# mainboard-raspi-2.net
KiCad netlist of a schematic drawn in EAGLE
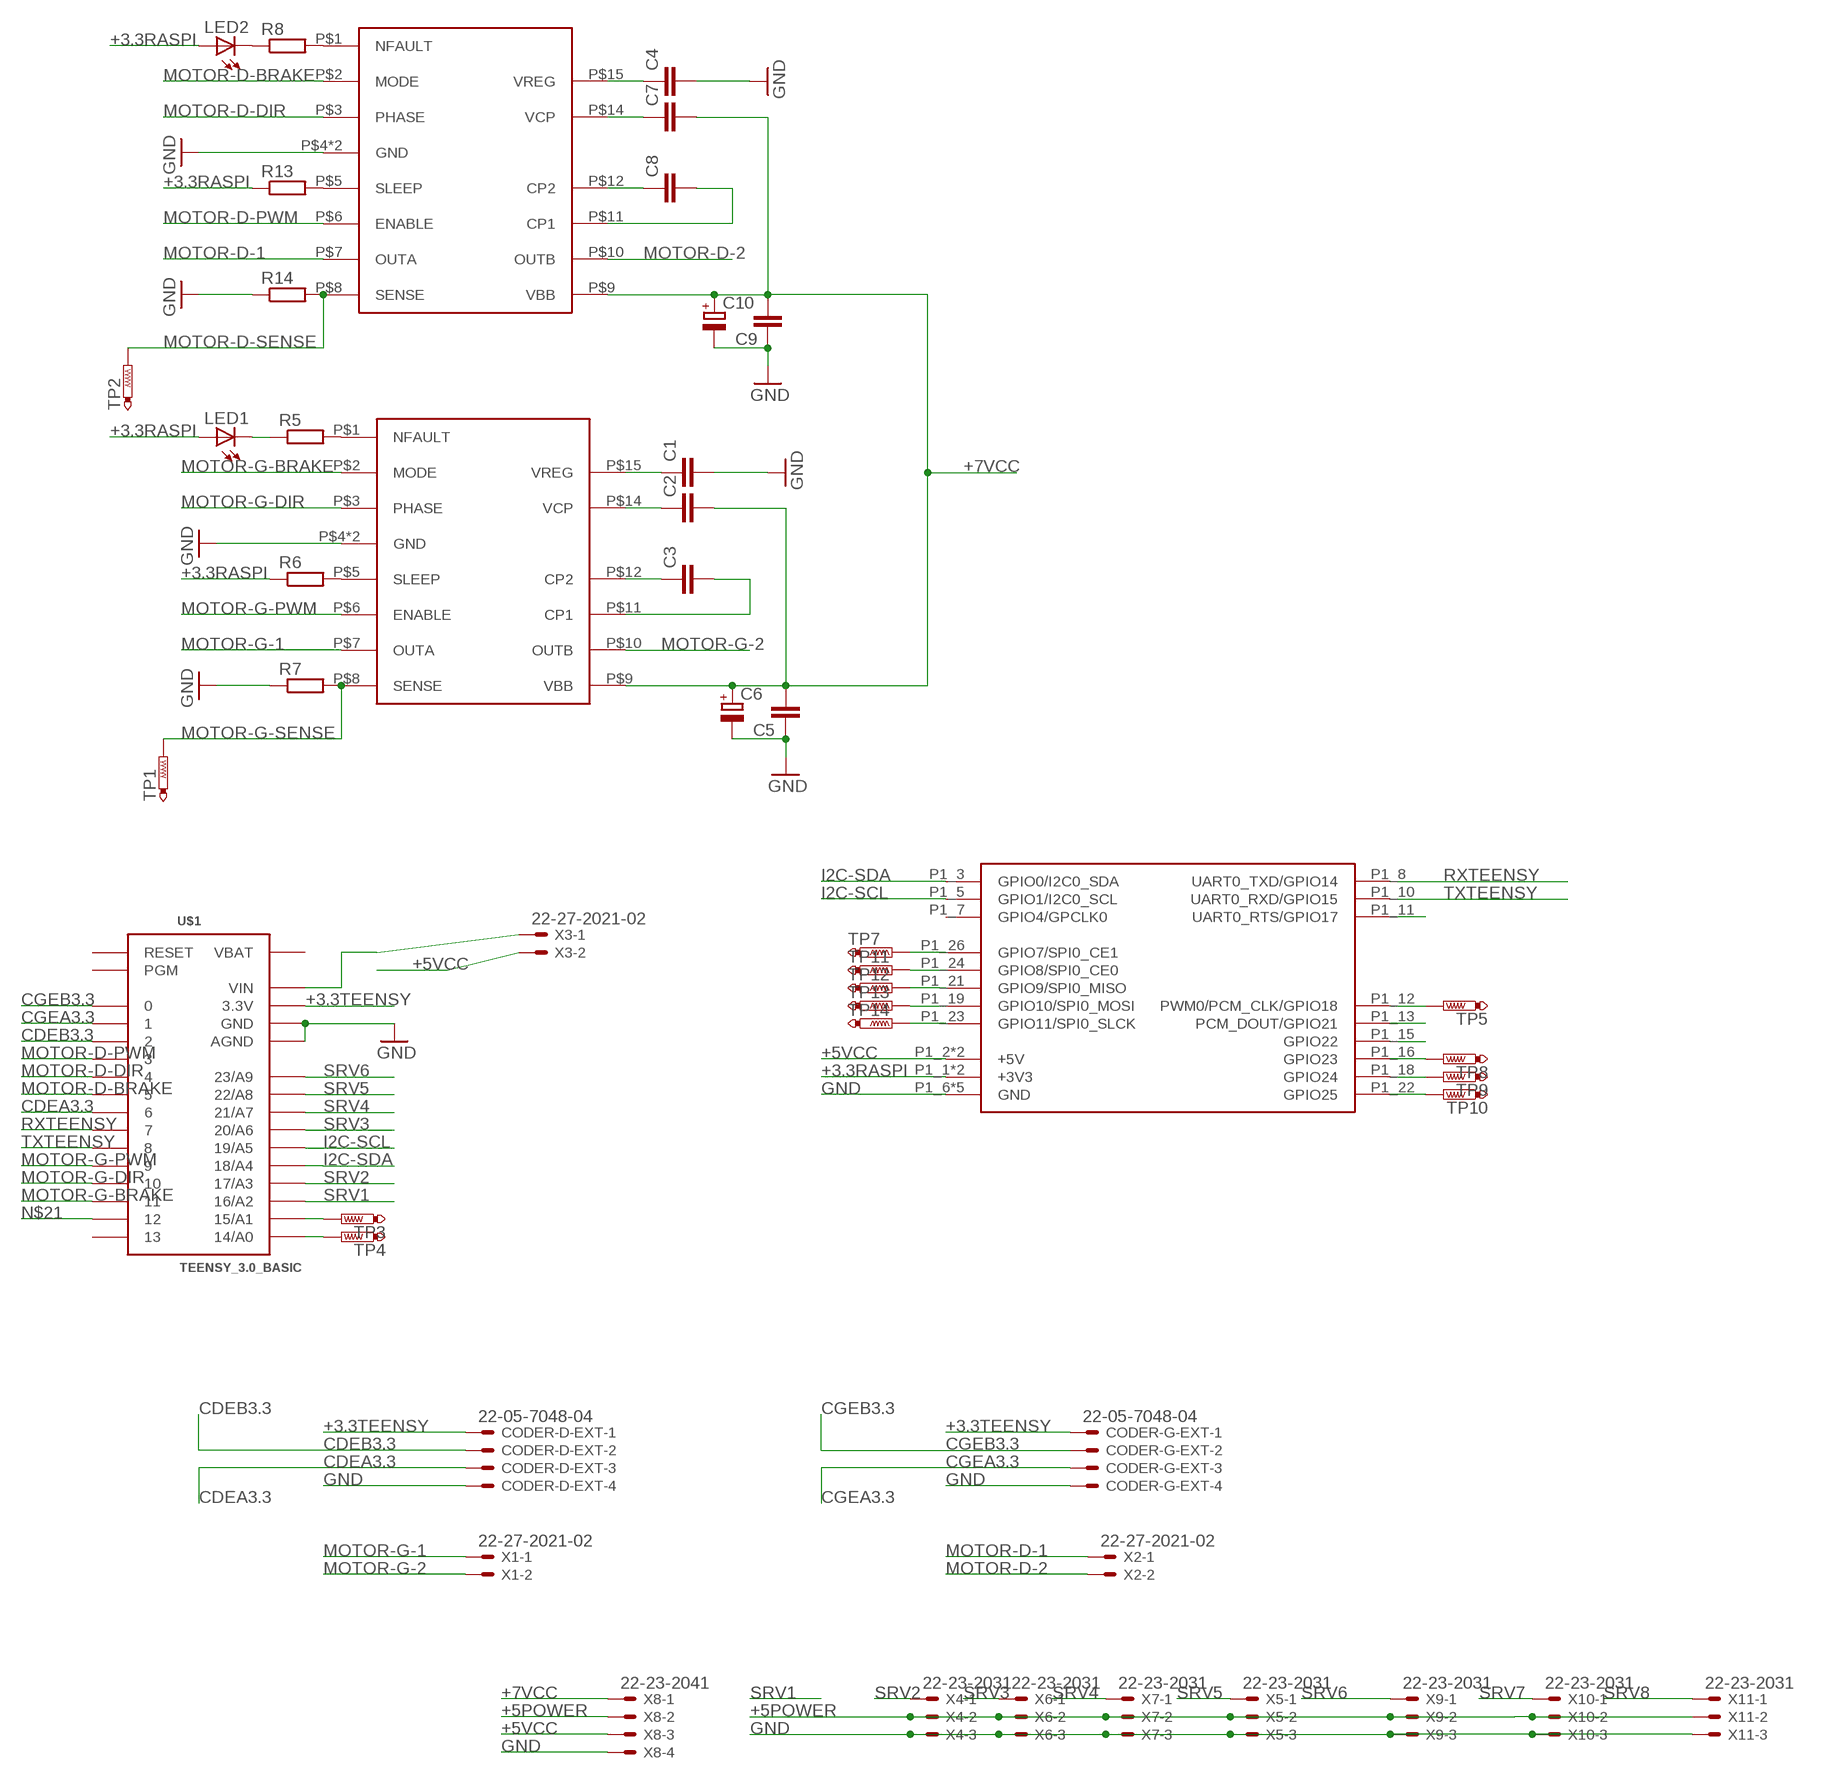
[diagram p0: schematic, sheet 1]

(export (version "E")
  (design (tool "Eeschema 10.0.6"))
  (components
    (comp (ref "C1")
      (value "C-EUC0805K")
      (footprint "eagle-import:C0805K")
      (libsource (lib "eagle-import") (part "C-EUC0805K"))
    )
    (comp (ref "C2")
      (value "C-EUC0805K")
      (footprint "eagle-import:C0805K")
      (libsource (lib "eagle-import") (part "C-EUC0805K"))
    )
    (comp (ref "C3")
      (value "C-EUC0805K")
      (footprint "eagle-import:C0805K")
      (libsource (lib "eagle-import") (part "C-EUC0805K"))
    )
    (comp (ref "C4")
      (value "C-EUC0805K")
      (footprint "eagle-import:C0805K")
      (libsource (lib "eagle-import") (part "C-EUC0805K"))
    )
    (comp (ref "C5")
      (value "C-EUC0805K")
      (footprint "eagle-import:C0805K")
      (libsource (lib "eagle-import") (part "C-EUC0805K"))
    )
    (comp (ref "C6")
      (value "CPOL-EUE3.5-8")
      (footprint "eagle-import:E3,5-8")
      (libsource (lib "eagle-import") (part "CPOL-EUE3.5-8"))
    )
    (comp (ref "C7")
      (value "C-EUC0805K")
      (footprint "eagle-import:C0805K")
      (libsource (lib "eagle-import") (part "C-EUC0805K"))
    )
    (comp (ref "C8")
      (value "C-EUC0805K")
      (footprint "eagle-import:C0805K")
      (libsource (lib "eagle-import") (part "C-EUC0805K"))
    )
    (comp (ref "C9")
      (value "C-EUC0805K")
      (footprint "eagle-import:C0805K")
      (libsource (lib "eagle-import") (part "C-EUC0805K"))
    )
    (comp (ref "C10")
      (value "CPOL-EUE3.5-8")
      (footprint "eagle-import:E3,5-8")
      (libsource (lib "eagle-import") (part "CPOL-EUE3.5-8"))
    )
    (comp (ref "CODER-D-EXT")
      (value "22-05-7048-04")
      (footprint "eagle-import:7395-04")
      (libsource (lib "eagle-import") (part "22-?-0405-7048"))
    )
    (comp (ref "CODER-G-EXT")
      (value "22-05-7048-04")
      (footprint "eagle-import:7395-04")
      (libsource (lib "eagle-import") (part "22-?-0405-7048"))
    )
    (comp (ref "LED1")
      (value "LED3MM")
      (footprint "eagle-import:LED3MM")
      (libsource (lib "eagle-import") (part "LED3MM"))
    )
    (comp (ref "LED2")
      (value "LED3MM")
      (footprint "eagle-import:LED3MM")
      (libsource (lib "eagle-import") (part "LED3MM"))
    )
    (comp (ref "R5")
      (value "R-EU_R0805W")
      (footprint "eagle-import:R0805W")
      (libsource (lib "eagle-import") (part "R-EU_R0805W"))
    )
    (comp (ref "R6")
      (value "R-EU_0204/7")
      (footprint "eagle-import:0204_7")
      (libsource (lib "eagle-import") (part "R-EU_0204/7"))
    )
    (comp (ref "R7")
      (value "R-EU_R0805W")
      (footprint "eagle-import:R0805W")
      (libsource (lib "eagle-import") (part "R-EU_R0805W"))
    )
    (comp (ref "R8")
      (value "R-EU_R0805W")
      (footprint "eagle-import:R0805W")
      (libsource (lib "eagle-import") (part "R-EU_R0805W"))
    )
    (comp (ref "R13")
      (value "R-EU_0204/7")
      (footprint "eagle-import:0204_7")
      (libsource (lib "eagle-import") (part "R-EU_0204/7"))
    )
    (comp (ref "R14")
      (value "R-EU_R0805W")
      (footprint "eagle-import:R0805W")
      (libsource (lib "eagle-import") (part "R-EU_R0805W"))
    )
    (comp (ref "TP1")
      (value "PTR1PAD1-13")
      (footprint "eagle-import:P1-13")
      (libsource (lib "eagle-import") (part "PTR1PAD1-13"))
    )
    (comp (ref "TP2")
      (value "PTR1PAD1-13")
      (footprint "eagle-import:P1-13")
      (libsource (lib "eagle-import") (part "PTR1PAD1-13"))
    )
    (comp (ref "TP3")
      (value "PTR1PAD1-13")
      (footprint "eagle-import:P1-13")
      (libsource (lib "eagle-import") (part "PTR1PAD1-13"))
    )
    (comp (ref "TP4")
      (value "PTR1PAD1-13")
      (footprint "eagle-import:P1-13")
      (libsource (lib "eagle-import") (part "PTR1PAD1-13"))
    )
    (comp (ref "TP5")
      (value "PTR1PAD1-13")
      (footprint "eagle-import:P1-13")
      (libsource (lib "eagle-import") (part "PTR1PAD1-13"))
    )
    (comp (ref "TP7")
      (value "PTR1PAD1-13")
      (footprint "eagle-import:P1-13")
      (libsource (lib "eagle-import") (part "PTR1PAD1-13"))
    )
    (comp (ref "TP8")
      (value "PTR1PAD1-13")
      (footprint "eagle-import:P1-13")
      (libsource (lib "eagle-import") (part "PTR1PAD1-13"))
    )
    (comp (ref "TP9")
      (value "PTR1PAD1-13")
      (footprint "eagle-import:P1-13")
      (libsource (lib "eagle-import") (part "PTR1PAD1-13"))
    )
    (comp (ref "TP10")
      (value "PTR1PAD1-13")
      (footprint "eagle-import:P1-13")
      (libsource (lib "eagle-import") (part "PTR1PAD1-13"))
    )
    (comp (ref "TP11")
      (value "PTR1PAD1-13")
      (footprint "eagle-import:P1-13")
      (libsource (lib "eagle-import") (part "PTR1PAD1-13"))
    )
    (comp (ref "TP12")
      (value "PTR1PAD1-13")
      (footprint "eagle-import:P1-13")
      (libsource (lib "eagle-import") (part "PTR1PAD1-13"))
    )
    (comp (ref "TP13")
      (value "PTR1PAD1-13")
      (footprint "eagle-import:P1-13")
      (libsource (lib "eagle-import") (part "PTR1PAD1-13"))
    )
    (comp (ref "TP14")
      (value "PTR1PAD1-13")
      (footprint "eagle-import:P1-13")
      (libsource (lib "eagle-import") (part "PTR1PAD1-13"))
    )
    (comp (ref "U$1")
      (value "TEENSY_3.0_BASIC")
      (footprint "eagle-import:TEENSY_3.0_BASIC")
      (libsource (lib "eagle-import") (part "TEENSY_3.0_BASIC"))
    )
    (comp (ref "U$3")
      (value "A3950-DIL")
      (footprint "eagle-import:DIL16")
      (libsource (lib "eagle-import") (part "A3950-DIL"))
    )
    (comp (ref "U$4")
      (value "A3950-DIL")
      (footprint "eagle-import:DIL16")
      (libsource (lib "eagle-import") (part "A3950-DIL"))
    )
    (comp (ref "U$5")
      (value "RPI-B-V1SHIELD")
      (footprint "eagle-import:RPI-B-V1-SHIELD")
      (libsource (lib "eagle-import") (part "RPI-B-V1SHIELD"))
    )
    (comp (ref "X1")
      (value "22-27-2021-02")
      (footprint "eagle-import:6410-02")
      (libsource (lib "eagle-import") (part "22-?-0227-2021"))
    )
    (comp (ref "X2")
      (value "22-27-2021-02")
      (footprint "eagle-import:6410-02")
      (libsource (lib "eagle-import") (part "22-?-0227-2021"))
    )
    (comp (ref "X3")
      (value "22-27-2021-02")
      (footprint "eagle-import:6410-02")
      (libsource (lib "eagle-import") (part "22-?-0227-2021"))
    )
    (comp (ref "X4")
      (value "22-23-2031")
      (footprint "eagle-import:22-23-2031")
      (fields (field (name "MF") "MOLEX"))
      (libsource (lib "eagle-import") (part "22-23-2031"))
    )
    (comp (ref "X5")
      (value "22-23-2031")
      (footprint "eagle-import:22-23-2031")
      (fields (field (name "MF") "MOLEX"))
      (libsource (lib "eagle-import") (part "22-23-2031"))
    )
    (comp (ref "X6")
      (value "22-23-2031")
      (footprint "eagle-import:22-23-2031")
      (fields (field (name "MF") "MOLEX"))
      (libsource (lib "eagle-import") (part "22-23-2031"))
    )
    (comp (ref "X7")
      (value "22-23-2031")
      (footprint "eagle-import:22-23-2031")
      (fields (field (name "MF") "MOLEX"))
      (libsource (lib "eagle-import") (part "22-23-2031"))
    )
    (comp (ref "X8")
      (value "22-23-2041")
      (footprint "eagle-import:22-23-2041")
      (fields (field (name "MF") "MOLEX"))
      (libsource (lib "eagle-import") (part "22-23-2041"))
    )
    (comp (ref "X9")
      (value "22-23-2031")
      (footprint "eagle-import:22-23-2031")
      (fields (field (name "MF") "MOLEX"))
      (libsource (lib "eagle-import") (part "22-23-2031"))
    )
    (comp (ref "X10")
      (value "22-23-2031")
      (footprint "eagle-import:22-23-2031")
      (fields (field (name "MF") "MOLEX"))
      (libsource (lib "eagle-import") (part "22-23-2031"))
    )
    (comp (ref "X11")
      (value "22-23-2031")
      (footprint "eagle-import:22-23-2031")
      (fields (field (name "MF") "MOLEX"))
      (libsource (lib "eagle-import") (part "22-23-2031"))
    )
  )
  (nets
    (net (code "1") (name "/+3.3RASPI") (class "Default")
      (node (ref "LED1") (pin "A") (pinfunction "A_A") (pintype "passive"))
      (node (ref "LED2") (pin "A") (pinfunction "A_A") (pintype "passive"))
      (node (ref "R13") (pin "1") (pinfunction "1_1") (pintype "passive"))
      (node (ref "R6") (pin "1") (pinfunction "1_1") (pintype "passive"))
      (node (ref "U$5") (pin "P1_1") (pinfunction "+3V3_P1_1") (pintype "power_in"))
      (node (ref "U$5") (pin "P1_17") (pinfunction "+3V3_P1_17") (pintype "power_in"))
    )
    (net (code "2") (name "/+3.3TEENSY") (class "Default")
      (node (ref "CODER-D-EXT") (pin "1") (pinfunction "S_1") (pintype "passive"))
      (node (ref "CODER-G-EXT") (pin "1") (pinfunction "S_1") (pintype "passive"))
      (node (ref "U$1") (pin "3.3V") (pinfunction "3.3V_3.3V") (pintype "power_in"))
      (node (ref "U$1") (pin "3.3V1") (pinfunction "3.3V_3.3V1") (pintype "power_in"))
    )
    (net (code "3") (name "/+5POWER") (class "Default")
      (node (ref "X10") (pin "2") (pinfunction "S_2") (pintype "passive"))
      (node (ref "X11") (pin "2") (pinfunction "S_2") (pintype "passive"))
      (node (ref "X4") (pin "2") (pinfunction "S_2") (pintype "passive"))
      (node (ref "X5") (pin "2") (pinfunction "S_2") (pintype "passive"))
      (node (ref "X6") (pin "2") (pinfunction "S_2") (pintype "passive"))
      (node (ref "X7") (pin "2") (pinfunction "S_2") (pintype "passive"))
      (node (ref "X8") (pin "2") (pinfunction "S_2") (pintype "passive"))
      (node (ref "X9") (pin "2") (pinfunction "S_2") (pintype "passive"))
    )
    (net (code "4") (name "/+5VCC") (class "Default")
      (node (ref "U$5") (pin "P1_2") (pinfunction "+5V_P1_2") (pintype "power_in"))
      (node (ref "U$5") (pin "P1_4") (pinfunction "+5V_P1_4") (pintype "power_in"))
      (node (ref "X3") (pin "2") (pinfunction "S_2") (pintype "passive"))
      (node (ref "X8") (pin "3") (pinfunction "S_3") (pintype "passive"))
    )
    (net (code "5") (name "/+7VCC") (class "Default")
      (node (ref "C10") (pin "+") (pinfunction "+_+") (pintype "passive"))
      (node (ref "C2") (pin "2") (pinfunction "2_2") (pintype "passive"))
      (node (ref "C5") (pin "2") (pinfunction "2_2") (pintype "passive"))
      (node (ref "C6") (pin "+") (pinfunction "+_+") (pintype "passive"))
      (node (ref "C7") (pin "2") (pinfunction "2_2") (pintype "passive"))
      (node (ref "C9") (pin "2") (pinfunction "2_2") (pintype "passive"))
      (node (ref "U$3") (pin "P$9") (pinfunction "VBB_P$9") (pintype "bidirectional"))
      (node (ref "U$4") (pin "P$9") (pinfunction "VBB_P$9") (pintype "bidirectional"))
      (node (ref "X8") (pin "1") (pinfunction "S_1") (pintype "passive"))
    )
    (net (code "6") (name "/CDEA3.3") (class "Default")
      (node (ref "CODER-D-EXT") (pin "3") (pinfunction "S_3") (pintype "passive"))
      (node (ref "U$1") (pin "6") (pinfunction "6_6") (pintype "bidirectional"))
    )
    (net (code "7") (name "/CDEB3.3") (class "Default")
      (node (ref "CODER-D-EXT") (pin "2") (pinfunction "S_2") (pintype "passive"))
      (node (ref "U$1") (pin "2") (pinfunction "2_2") (pintype "bidirectional"))
    )
    (net (code "8") (name "/CGEA3.3") (class "Default")
      (node (ref "CODER-G-EXT") (pin "3") (pinfunction "S_3") (pintype "passive"))
      (node (ref "U$1") (pin "1") (pinfunction "1_1") (pintype "bidirectional"))
    )
    (net (code "9") (name "/CGEB3.3") (class "Default")
      (node (ref "CODER-G-EXT") (pin "2") (pinfunction "S_2") (pintype "passive"))
      (node (ref "U$1") (pin "0") (pinfunction "0_0") (pintype "bidirectional"))
    )
    (net (code "10") (name "/I2C-SCL") (class "Default")
      (node (ref "U$1") (pin "19/A5") (pinfunction "19/A5_19/A5") (pintype "bidirectional"))
      (node (ref "U$5") (pin "P1_5") (pinfunction "GPIO1/I2C0_SCL_P1_5") (pintype "bidirectional"))
    )
    (net (code "11") (name "/I2C-SDA") (class "Default")
      (node (ref "U$1") (pin "18/A4") (pinfunction "18/A4_18/A4") (pintype "bidirectional"))
      (node (ref "U$5") (pin "P1_3") (pinfunction "GPIO0/I2C0_SDA_P1_3") (pintype "bidirectional"))
    )
    (net (code "12") (name "/MOTOR-D-1") (class "Default")
      (node (ref "U$4") (pin "P$7") (pinfunction "OUTA_P$7") (pintype "bidirectional"))
      (node (ref "X2") (pin "1") (pinfunction "S_1") (pintype "passive"))
    )
    (net (code "13") (name "/MOTOR-D-2") (class "Default")
      (node (ref "U$4") (pin "P$10") (pinfunction "OUTB_P$10") (pintype "bidirectional"))
      (node (ref "X2") (pin "2") (pinfunction "S_2") (pintype "passive"))
    )
    (net (code "14") (name "/MOTOR-D-BRAKE") (class "Default")
      (node (ref "U$1") (pin "5") (pinfunction "5_5") (pintype "bidirectional"))
      (node (ref "U$4") (pin "P$2") (pinfunction "MODE_P$2") (pintype "bidirectional"))
    )
    (net (code "15") (name "/MOTOR-D-DIR") (class "Default")
      (node (ref "U$1") (pin "4") (pinfunction "4_4") (pintype "bidirectional"))
      (node (ref "U$4") (pin "P$3") (pinfunction "PHASE_P$3") (pintype "bidirectional"))
    )
    (net (code "16") (name "/MOTOR-D-PWM") (class "Default")
      (node (ref "U$1") (pin "3") (pinfunction "3_3") (pintype "bidirectional"))
      (node (ref "U$4") (pin "P$6") (pinfunction "ENABLE_P$6") (pintype "bidirectional"))
    )
    (net (code "17") (name "/MOTOR-D-SENSE") (class "Default")
      (node (ref "R14") (pin "2") (pinfunction "2_2") (pintype "passive"))
      (node (ref "TP2") (pin "TP") (pinfunction "TP_TP") (pintype "input"))
      (node (ref "U$4") (pin "P$8") (pinfunction "SENSE_P$8") (pintype "bidirectional"))
    )
    (net (code "18") (name "/MOTOR-G-1") (class "Default")
      (node (ref "U$3") (pin "P$7") (pinfunction "OUTA_P$7") (pintype "bidirectional"))
      (node (ref "X1") (pin "1") (pinfunction "S_1") (pintype "passive"))
    )
    (net (code "19") (name "/MOTOR-G-2") (class "Default")
      (node (ref "U$3") (pin "P$10") (pinfunction "OUTB_P$10") (pintype "bidirectional"))
      (node (ref "X1") (pin "2") (pinfunction "S_2") (pintype "passive"))
    )
    (net (code "20") (name "/MOTOR-G-BRAKE") (class "Default")
      (node (ref "U$1") (pin "11") (pinfunction "11_11") (pintype "bidirectional"))
      (node (ref "U$3") (pin "P$2") (pinfunction "MODE_P$2") (pintype "bidirectional"))
    )
    (net (code "21") (name "/MOTOR-G-DIR") (class "Default")
      (node (ref "U$1") (pin "10") (pinfunction "10_10") (pintype "bidirectional"))
      (node (ref "U$3") (pin "P$3") (pinfunction "PHASE_P$3") (pintype "bidirectional"))
    )
    (net (code "22") (name "/MOTOR-G-PWM") (class "Default")
      (node (ref "U$1") (pin "9") (pinfunction "9_9") (pintype "bidirectional"))
      (node (ref "U$3") (pin "P$6") (pinfunction "ENABLE_P$6") (pintype "bidirectional"))
    )
    (net (code "23") (name "/MOTOR-G-SENSE") (class "Default")
      (node (ref "R7") (pin "2") (pinfunction "2_2") (pintype "passive"))
      (node (ref "TP1") (pin "TP") (pinfunction "TP_TP") (pintype "input"))
      (node (ref "U$3") (pin "P$8") (pinfunction "SENSE_P$8") (pintype "bidirectional"))
    )
    (net (code "24") (name "/N$21") (class "Default")
      (node (ref "U$1") (pin "12") (pinfunction "12_12") (pintype "bidirectional"))
    )
    (net (code "25") (name "/RXTEENSY") (class "Default")
      (node (ref "U$1") (pin "7") (pinfunction "7_7") (pintype "bidirectional"))
      (node (ref "U$5") (pin "P1_8") (pinfunction "UART0_TXD/GPIO14_P1_8") (pintype "bidirectional"))
    )
    (net (code "26") (name "/SRV1") (class "Default")
      (node (ref "U$1") (pin "16/A2") (pinfunction "16/A2_16/A2") (pintype "bidirectional"))
    )
    (net (code "27") (name "/SRV2") (class "Default")
      (node (ref "U$1") (pin "17/A3") (pinfunction "17/A3_17/A3") (pintype "bidirectional"))
      (node (ref "X4") (pin "1") (pinfunction "S_1") (pintype "passive"))
    )
    (net (code "28") (name "/SRV3") (class "Default")
      (node (ref "U$1") (pin "20/A6") (pinfunction "20/A6_20/A6") (pintype "bidirectional"))
      (node (ref "X6") (pin "1") (pinfunction "S_1") (pintype "passive"))
    )
    (net (code "29") (name "/SRV4") (class "Default")
      (node (ref "U$1") (pin "21/A7") (pinfunction "21/A7_21/A7") (pintype "bidirectional"))
      (node (ref "X7") (pin "1") (pinfunction "S_1") (pintype "passive"))
    )
    (net (code "30") (name "/SRV5") (class "Default")
      (node (ref "U$1") (pin "22/A8") (pinfunction "22/A8_22/A8") (pintype "bidirectional"))
      (node (ref "X5") (pin "1") (pinfunction "S_1") (pintype "passive"))
    )
    (net (code "31") (name "/SRV6") (class "Default")
      (node (ref "U$1") (pin "23/A9") (pinfunction "23/A9_23/A9") (pintype "bidirectional"))
      (node (ref "X9") (pin "1") (pinfunction "S_1") (pintype "passive"))
    )
    (net (code "32") (name "/SRV7") (class "Default")
      (node (ref "X10") (pin "1") (pinfunction "S_1") (pintype "passive"))
    )
    (net (code "33") (name "/SRV8") (class "Default")
      (node (ref "X11") (pin "1") (pinfunction "S_1") (pintype "passive"))
    )
    (net (code "34") (name "/TXTEENSY") (class "Default")
      (node (ref "U$1") (pin "8") (pinfunction "8_8") (pintype "bidirectional"))
      (node (ref "U$5") (pin "P1_10") (pinfunction "UART0_RXD/GPIO15_P1_10") (pintype "bidirectional"))
    )
    (net (code "35") (name "/VBAT") (class "Default")
      (node (ref "U$1") (pin "VBAT") (pinfunction "VBAT_VBAT") (pintype "power_in"))
    )
    (net (code "36") (name "GND") (class "Default")
      (node (ref "C1") (pin "2") (pinfunction "2_2") (pintype "passive"))
      (node (ref "C10") (pin "-") (pinfunction "-_-") (pintype "passive"))
      (node (ref "C4") (pin "2") (pinfunction "2_2") (pintype "passive"))
      (node (ref "C5") (pin "1") (pinfunction "1_1") (pintype "passive"))
      (node (ref "C6") (pin "-") (pinfunction "-_-") (pintype "passive"))
      (node (ref "C9") (pin "1") (pinfunction "1_1") (pintype "passive"))
      (node (ref "CODER-D-EXT") (pin "4") (pinfunction "S_4") (pintype "passive"))
      (node (ref "CODER-G-EXT") (pin "4") (pinfunction "S_4") (pintype "passive"))
      (node (ref "R14") (pin "1") (pinfunction "1_1") (pintype "passive"))
      (node (ref "R7") (pin "1") (pinfunction "1_1") (pintype "passive"))
      (node (ref "U$1") (pin "AGND") (pinfunction "AGND_AGND") (pintype "power_in"))
      (node (ref "U$1") (pin "GND") (pinfunction "GND_GND") (pintype "power_in"))
      (node (ref "U$1") (pin "GND1") (pinfunction "GND_GND1") (pintype "power_in"))
      (node (ref "U$3") (pin "P$13") (pinfunction "GND_P$13") (pintype "bidirectional"))
      (node (ref "U$3") (pin "P$4") (pinfunction "GND_P$4") (pintype "bidirectional"))
      (node (ref "U$4") (pin "P$13") (pinfunction "GND_P$13") (pintype "bidirectional"))
      (node (ref "U$4") (pin "P$4") (pinfunction "GND_P$4") (pintype "bidirectional"))
      (node (ref "U$5") (pin "P1_14") (pinfunction "GND_P1_14") (pintype "power_in"))
      (node (ref "U$5") (pin "P1_20") (pinfunction "GND_P1_20") (pintype "power_in"))
      (node (ref "U$5") (pin "P1_25") (pinfunction "GND_P1_25") (pintype "power_in"))
      (node (ref "U$5") (pin "P1_6") (pinfunction "GND_P1_6") (pintype "power_in"))
      (node (ref "U$5") (pin "P1_9") (pinfunction "GND_P1_9") (pintype "power_in"))
      (node (ref "X10") (pin "3") (pinfunction "S_3") (pintype "passive"))
      (node (ref "X11") (pin "3") (pinfunction "S_3") (pintype "passive"))
      (node (ref "X4") (pin "3") (pinfunction "S_3") (pintype "passive"))
      (node (ref "X5") (pin "3") (pinfunction "S_3") (pintype "passive"))
      (node (ref "X6") (pin "3") (pinfunction "S_3") (pintype "passive"))
      (node (ref "X7") (pin "3") (pinfunction "S_3") (pintype "passive"))
      (node (ref "X8") (pin "4") (pinfunction "S_4") (pintype "passive"))
      (node (ref "X9") (pin "3") (pinfunction "S_3") (pintype "passive"))
    )
    (net (code "37") (name "Net-(LED1-C)") (class "Default")
      (node (ref "LED1") (pin "K") (pinfunction "C_K") (pintype "passive"))
      (node (ref "R5") (pin "1") (pinfunction "1_1") (pintype "passive"))
    )
    (net (code "38") (name "Net-(LED2-C)") (class "Default")
      (node (ref "LED2") (pin "K") (pinfunction "C_K") (pintype "passive"))
      (node (ref "R8") (pin "1") (pinfunction "1_1") (pintype "passive"))
    )
    (net (code "39") (name "Net-(TP3-PadTP)") (class "Default")
      (node (ref "TP3") (pin "TP") (pinfunction "TP_TP") (pintype "input"))
      (node (ref "U$1") (pin "15/A1") (pinfunction "15/A1_15/A1") (pintype "bidirectional"))
    )
    (net (code "40") (name "Net-(TP4-PadTP)") (class "Default")
      (node (ref "TP4") (pin "TP") (pinfunction "TP_TP") (pintype "input"))
      (node (ref "U$1") (pin "14/A0") (pinfunction "14/A0_14/A0") (pintype "bidirectional"))
    )
    (net (code "41") (name "Net-(U$3-CP1)") (class "Default")
      (node (ref "C3") (pin "2") (pinfunction "2_2") (pintype "passive"))
      (node (ref "U$3") (pin "P$11") (pinfunction "CP1_P$11") (pintype "bidirectional"))
    )
    (net (code "42") (name "Net-(U$3-CP2)") (class "Default")
      (node (ref "C3") (pin "1") (pinfunction "1_1") (pintype "passive"))
      (node (ref "U$3") (pin "P$12") (pinfunction "CP2_P$12") (pintype "bidirectional"))
    )
    (net (code "43") (name "Net-(U$3-NFAULT)") (class "Default")
      (node (ref "R5") (pin "2") (pinfunction "2_2") (pintype "passive"))
      (node (ref "U$3") (pin "P$1") (pinfunction "NFAULT_P$1") (pintype "bidirectional"))
    )
    (net (code "44") (name "Net-(U$3-SLEEP)") (class "Default")
      (node (ref "R6") (pin "2") (pinfunction "2_2") (pintype "passive"))
      (node (ref "U$3") (pin "P$5") (pinfunction "SLEEP_P$5") (pintype "bidirectional"))
    )
    (net (code "45") (name "Net-(U$3-VCP)") (class "Default")
      (node (ref "C2") (pin "1") (pinfunction "1_1") (pintype "passive"))
      (node (ref "U$3") (pin "P$14") (pinfunction "VCP_P$14") (pintype "bidirectional"))
    )
    (net (code "46") (name "Net-(U$3-VREG)") (class "Default")
      (node (ref "C1") (pin "1") (pinfunction "1_1") (pintype "passive"))
      (node (ref "U$3") (pin "P$15") (pinfunction "VREG_P$15") (pintype "bidirectional"))
    )
    (net (code "47") (name "Net-(U$4-CP1)") (class "Default")
      (node (ref "C8") (pin "2") (pinfunction "2_2") (pintype "passive"))
      (node (ref "U$4") (pin "P$11") (pinfunction "CP1_P$11") (pintype "bidirectional"))
    )
    (net (code "48") (name "Net-(U$4-CP2)") (class "Default")
      (node (ref "C8") (pin "1") (pinfunction "1_1") (pintype "passive"))
      (node (ref "U$4") (pin "P$12") (pinfunction "CP2_P$12") (pintype "bidirectional"))
    )
    (net (code "49") (name "Net-(U$4-NFAULT)") (class "Default")
      (node (ref "R8") (pin "2") (pinfunction "2_2") (pintype "passive"))
      (node (ref "U$4") (pin "P$1") (pinfunction "NFAULT_P$1") (pintype "bidirectional"))
    )
    (net (code "50") (name "Net-(U$4-SLEEP)") (class "Default")
      (node (ref "R13") (pin "2") (pinfunction "2_2") (pintype "passive"))
      (node (ref "U$4") (pin "P$5") (pinfunction "SLEEP_P$5") (pintype "bidirectional"))
    )
    (net (code "51") (name "Net-(U$4-VCP)") (class "Default")
      (node (ref "C7") (pin "1") (pinfunction "1_1") (pintype "passive"))
      (node (ref "U$4") (pin "P$14") (pinfunction "VCP_P$14") (pintype "bidirectional"))
    )
    (net (code "52") (name "Net-(U$4-VREG)") (class "Default")
      (node (ref "C4") (pin "1") (pinfunction "1_1") (pintype "passive"))
      (node (ref "U$4") (pin "P$15") (pinfunction "VREG_P$15") (pintype "bidirectional"))
    )
    (net (code "53") (name "Net-(U$5-GPIO7{slash}SPI0_CE1)") (class "Default")
      (node (ref "TP7") (pin "TP") (pinfunction "TP_TP") (pintype "input"))
      (node (ref "U$5") (pin "P1_26") (pinfunction "GPIO7/SPI0_CE1_P1_26") (pintype "bidirectional"))
    )
    (net (code "54") (name "Net-(U$5-GPIO8{slash}SPI0_CE0)") (class "Default")
      (node (ref "TP11") (pin "TP") (pinfunction "TP_TP") (pintype "input"))
      (node (ref "U$5") (pin "P1_24") (pinfunction "GPIO8/SPI0_CE0_P1_24") (pintype "bidirectional"))
    )
    (net (code "55") (name "Net-(U$5-GPIO9{slash}SPI0_MISO)") (class "Default")
      (node (ref "TP12") (pin "TP") (pinfunction "TP_TP") (pintype "input"))
      (node (ref "U$5") (pin "P1_21") (pinfunction "GPIO9/SPI0_MISO_P1_21") (pintype "bidirectional"))
    )
    (net (code "56") (name "Net-(U$5-GPIO10{slash}SPI0_MOSI)") (class "Default")
      (node (ref "TP13") (pin "TP") (pinfunction "TP_TP") (pintype "input"))
      (node (ref "U$5") (pin "P1_19") (pinfunction "GPIO10/SPI0_MOSI_P1_19") (pintype "bidirectional"))
    )
    (net (code "57") (name "Net-(U$5-GPIO11{slash}SPI0_SLCK)") (class "Default")
      (node (ref "TP14") (pin "TP") (pinfunction "TP_TP") (pintype "input"))
      (node (ref "U$5") (pin "P1_23") (pinfunction "GPIO11/SPI0_SLCK_P1_23") (pintype "bidirectional"))
    )
    (net (code "58") (name "Net-(U$5-GPIO23)") (class "Default")
      (node (ref "TP8") (pin "TP") (pinfunction "TP_TP") (pintype "input"))
      (node (ref "U$5") (pin "P1_16") (pinfunction "GPIO23_P1_16") (pintype "bidirectional"))
    )
    (net (code "59") (name "Net-(U$5-GPIO24)") (class "Default")
      (node (ref "TP9") (pin "TP") (pinfunction "TP_TP") (pintype "input"))
      (node (ref "U$5") (pin "P1_18") (pinfunction "GPIO24_P1_18") (pintype "bidirectional"))
    )
    (net (code "60") (name "Net-(U$5-GPIO25)") (class "Default")
      (node (ref "TP10") (pin "TP") (pinfunction "TP_TP") (pintype "input"))
      (node (ref "U$5") (pin "P1_22") (pinfunction "GPIO25_P1_22") (pintype "bidirectional"))
    )
    (net (code "61") (name "Net-(U$5-PWM0{slash}PCM_CLK{slash}GPIO18)") (class "Default")
      (node (ref "TP5") (pin "TP") (pinfunction "TP_TP") (pintype "input"))
      (node (ref "U$5") (pin "P1_12") (pinfunction "PWM0/PCM_CLK/GPIO18_P1_12") (pintype "bidirectional"))
    )
    (net (code "62") (name "Net-(X3A-S)") (class "Default")
      (node (ref "U$1") (pin "VIN") (pinfunction "VIN_VIN") (pintype "power_in"))
      (node (ref "X3") (pin "1") (pinfunction "S_1") (pintype "passive"))
    )
    (net (code "63") (name "unconnected-(U$1-Pad13)") (class "Default")
      (node (ref "U$1") (pin "13") (pinfunction "13_13") (pintype "bidirectional"))
    )
    (net (code "64") (name "unconnected-(U$1-PadPGM)") (class "Default")
      (node (ref "U$1") (pin "PGM") (pinfunction "PGM_PGM") (pintype "bidirectional"))
    )
    (net (code "65") (name "unconnected-(U$1-PadRESET)") (class "Default")
      (node (ref "U$1") (pin "RESET") (pinfunction "RESET_RESET") (pintype "bidirectional"))
    )
    (net (code "66") (name "unconnected-(U$5-GPIO4{slash}GPCLK0-PadP1_7)") (class "Default")
      (node (ref "U$5") (pin "P1_7") (pinfunction "GPIO4/GPCLK0_P1_7") (pintype "bidirectional"))
    )
    (net (code "67") (name "unconnected-(U$5-GPIO22-PadP1_15)") (class "Default")
      (node (ref "U$5") (pin "P1_15") (pinfunction "GPIO22_P1_15") (pintype "bidirectional"))
    )
    (net (code "68") (name "unconnected-(U$5-PCM_DOUT{slash}GPIO21-PadP1_13)") (class "Default")
      (node (ref "U$5") (pin "P1_13") (pinfunction "PCM_DOUT/GPIO21_P1_13") (pintype "bidirectional"))
    )
    (net (code "69") (name "unconnected-(U$5-UART0_RTS{slash}GPIO17-PadP1_11)") (class "Default")
      (node (ref "U$5") (pin "P1_11") (pinfunction "UART0_RTS/GPIO17_P1_11") (pintype "bidirectional"))
    )
  )
)
